# Mechanical_Bridges_AFE.net
KiCad netlist of a schematic drawn in Altium Designer
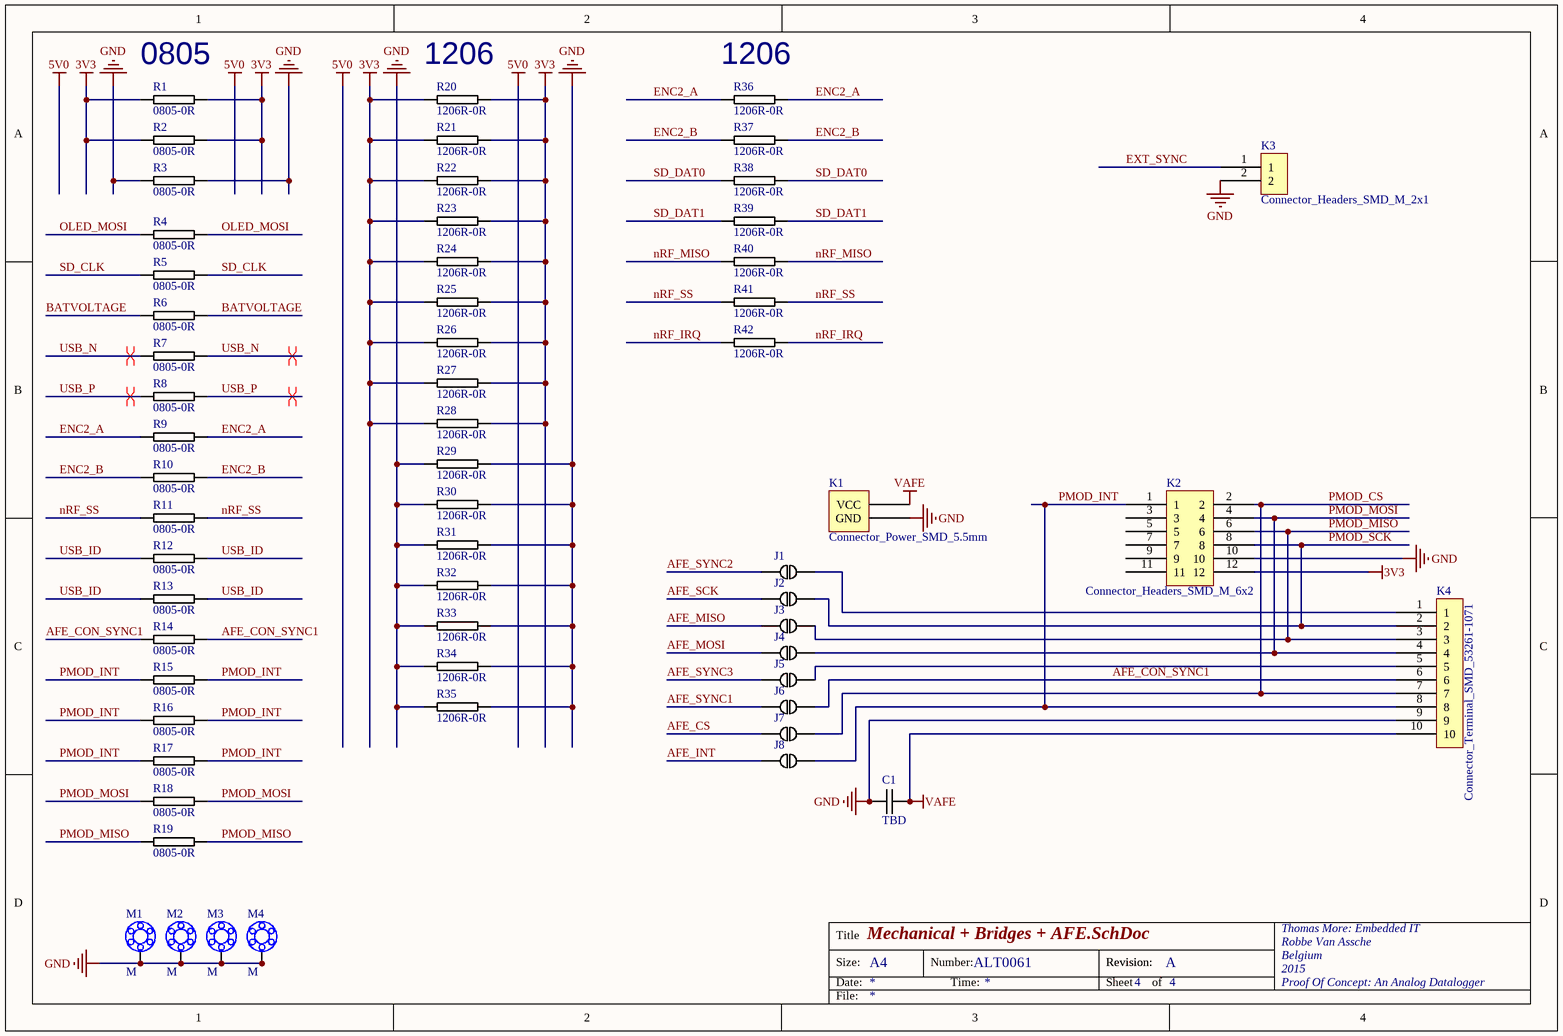
[diagram p0: Mechanical + Bridges + AFE.SchDoc]

(export (version "E")
  (design (tool "Eeschema 10.0.6"))
  (components
    (comp (ref "C1")
      (value "TBD")
      (footprint "1210C-GENERIC")
      (description "CAPACITOR 1210 CERAMIC VALUE TO BE DETERMINED")
      (libsource (lib "RVA_Altium_Library") (part "Passives_Capacitors_1210_1210C-TBD"))
    )
    (comp (ref "J1")
      (value "Connector_Production Connectors_SMD_BYPASS")
      (footprint "BYPASS")
      (description "SOLDERDOT BYPASS")
      (libsource (lib "RVA_Altium_Library") (part "Connector_Production Connectors_SMD_BYPASS"))
    )
    (comp (ref "J2")
      (value "Connector_Production Connectors_SMD_BYPASS")
      (footprint "BYPASS")
      (description "SOLDERDOT BYPASS")
      (libsource (lib "RVA_Altium_Library") (part "Connector_Production Connectors_SMD_BYPASS"))
    )
    (comp (ref "J3")
      (value "Connector_Production Connectors_SMD_BYPASS")
      (footprint "BYPASS")
      (description "SOLDERDOT BYPASS")
      (libsource (lib "RVA_Altium_Library") (part "Connector_Production Connectors_SMD_BYPASS"))
    )
    (comp (ref "J4")
      (value "Connector_Production Connectors_SMD_BYPASS")
      (footprint "BYPASS")
      (description "SOLDERDOT BYPASS")
      (libsource (lib "RVA_Altium_Library") (part "Connector_Production Connectors_SMD_BYPASS"))
    )
    (comp (ref "J5")
      (value "Connector_Production Connectors_SMD_BYPASS")
      (footprint "BYPASS")
      (description "SOLDERDOT BYPASS")
      (libsource (lib "RVA_Altium_Library") (part "Connector_Production Connectors_SMD_BYPASS"))
    )
    (comp (ref "J6")
      (value "Connector_Production Connectors_SMD_BYPASS")
      (footprint "BYPASS")
      (description "SOLDERDOT BYPASS")
      (libsource (lib "RVA_Altium_Library") (part "Connector_Production Connectors_SMD_BYPASS"))
    )
    (comp (ref "J7")
      (value "Connector_Production Connectors_SMD_BYPASS")
      (footprint "BYPASS")
      (description "SOLDERDOT BYPASS")
      (libsource (lib "RVA_Altium_Library") (part "Connector_Production Connectors_SMD_BYPASS"))
    )
    (comp (ref "J8")
      (value "Connector_Production Connectors_SMD_BYPASS")
      (footprint "BYPASS")
      (description "SOLDERDOT BYPASS")
      (libsource (lib "RVA_Altium_Library") (part "Connector_Production Connectors_SMD_BYPASS"))
    )
    (comp (ref "K1")
      (value "Connector_Power_SMD_5.5mm")
      (footprint "ADC-028")
      (description "5.5mm SMD")
      (libsource (lib "RVA_Altium_Library") (part "Connector_Power_SMD_5.5mm"))
    )
    (comp (ref "K2")
      (value "Connector_Headers_SMD_M_6x2")
      (footprint "Header_Male_2.54 6x2")
      (description "SMD Header 6x2")
      (libsource (lib "RVA_Altium_Library") (part "Connector_Headers_SMD_M_6x2"))
    )
    (comp (ref "K3")
      (value "Connector_Headers_SMD_M_2x1")
      (footprint "Header_Male_2.54 2x1")
      (description "SMD Header 2x1")
      (libsource (lib "RVA_Altium_Library") (part "Connector_Headers_SMD_M_2x1"))
    )
    (comp (ref "K4")
      (value "Connector_Terminal_SMD_53261-1071")
      (footprint "53261-1071")
      (description "Picoblade 10p")
      (libsource (lib "RVA_Altium_Library") (part "Connector_Terminal_SMD_53261-1071"))
    )
    (comp (ref "M1")
      (value "M")
      (footprint "MOUNTING")
      (description "MOUNTING HOLE - NON INSTALLABLE")
      (libsource (lib "vh_altium_library") (part "MOUNTING"))
    )
    (comp (ref "M2")
      (value "M")
      (footprint "MOUNTING")
      (description "MOUNTING HOLE - NON INSTALLABLE")
      (libsource (lib "vh_altium_library") (part "MOUNTING"))
    )
    (comp (ref "M3")
      (value "M")
      (footprint "MOUNTING")
      (description "MOUNTING HOLE - NON INSTALLABLE")
      (libsource (lib "vh_altium_library") (part "MOUNTING"))
    )
    (comp (ref "M4")
      (value "M")
      (footprint "MOUNTING")
      (description "MOUNTING HOLE - NON INSTALLABLE")
      (libsource (lib "vh_altium_library") (part "MOUNTING"))
    )
    (comp (ref "R1")
      (value "0805-0R")
      (footprint "0805R-GENERIC")
      (description "RESISTOR 0805 1 WATT")
      (libsource (lib "RVA_Altium_Library") (part "0805R-0R"))
    )
    (comp (ref "R2")
      (value "0805-0R")
      (footprint "0805R-GENERIC")
      (description "RESISTOR 0805 1 WATT")
      (libsource (lib "RVA_Altium_Library") (part "0805R-0R"))
    )
    (comp (ref "R3")
      (value "0805-0R")
      (footprint "0805R-GENERIC")
      (description "RESISTOR 0805 1 WATT")
      (libsource (lib "RVA_Altium_Library") (part "0805R-0R"))
    )
    (comp (ref "R4")
      (value "0805-0R")
      (footprint "0805R-GENERIC")
      (description "RESISTOR 0805 1 WATT")
      (libsource (lib "RVA_Altium_Library") (part "0805R-0R"))
    )
    (comp (ref "R5")
      (value "0805-0R")
      (footprint "0805R-GENERIC")
      (description "RESISTOR 0805 1 WATT")
      (libsource (lib "RVA_Altium_Library") (part "0805R-0R"))
    )
    (comp (ref "R6")
      (value "0805-0R")
      (footprint "0805R-GENERIC")
      (description "RESISTOR 0805 1 WATT")
      (libsource (lib "RVA_Altium_Library") (part "0805R-0R"))
    )
    (comp (ref "R7")
      (value "0805-0R")
      (footprint "0805R-GENERIC")
      (description "RESISTOR 0805 1 WATT")
      (libsource (lib "RVA_Altium_Library") (part "0805R-0R"))
    )
    (comp (ref "R8")
      (value "0805-0R")
      (footprint "0805R-GENERIC")
      (description "RESISTOR 0805 1 WATT")
      (libsource (lib "RVA_Altium_Library") (part "0805R-0R"))
    )
    (comp (ref "R9")
      (value "0805-0R")
      (footprint "0805R-GENERIC")
      (description "RESISTOR 0805 1 WATT")
      (libsource (lib "RVA_Altium_Library") (part "0805R-0R"))
    )
    (comp (ref "R10")
      (value "0805-0R")
      (footprint "0805R-GENERIC")
      (description "RESISTOR 0805 1 WATT")
      (libsource (lib "RVA_Altium_Library") (part "0805R-0R"))
    )
    (comp (ref "R11")
      (value "0805-0R")
      (footprint "0805R-GENERIC")
      (description "RESISTOR 0805 1 WATT")
      (libsource (lib "RVA_Altium_Library") (part "0805R-0R"))
    )
    (comp (ref "R12")
      (value "0805-0R")
      (footprint "0805R-GENERIC")
      (description "RESISTOR 0805 1 WATT")
      (libsource (lib "RVA_Altium_Library") (part "0805R-0R"))
    )
    (comp (ref "R13")
      (value "0805-0R")
      (footprint "0805R-GENERIC")
      (description "RESISTOR 0805 1 WATT")
      (libsource (lib "RVA_Altium_Library") (part "0805R-0R"))
    )
    (comp (ref "R14")
      (value "0805-0R")
      (footprint "0805R-GENERIC")
      (description "RESISTOR 0805 1 WATT")
      (libsource (lib "RVA_Altium_Library") (part "0805R-0R"))
    )
    (comp (ref "R15")
      (value "0805-0R")
      (footprint "0805R-GENERIC")
      (description "RESISTOR 0805 1 WATT")
      (libsource (lib "RVA_Altium_Library") (part "0805R-0R"))
    )
    (comp (ref "R16")
      (value "0805-0R")
      (footprint "0805R-GENERIC")
      (description "RESISTOR 0805 1 WATT")
      (libsource (lib "RVA_Altium_Library") (part "0805R-0R"))
    )
    (comp (ref "R17")
      (value "0805-0R")
      (footprint "0805R-GENERIC")
      (description "RESISTOR 0805 1 WATT")
      (libsource (lib "RVA_Altium_Library") (part "0805R-0R"))
    )
    (comp (ref "R18")
      (value "0805-0R")
      (footprint "0805R-GENERIC")
      (description "RESISTOR 0805 1 WATT")
      (libsource (lib "RVA_Altium_Library") (part "0805R-0R"))
    )
    (comp (ref "R19")
      (value "0805-0R")
      (footprint "0805R-GENERIC")
      (description "RESISTOR 0805 1 WATT")
      (libsource (lib "RVA_Altium_Library") (part "0805R-0R"))
    )
    (comp (ref "R20")
      (value "1206R-0R")
      (footprint "1206R-GENERIC")
      (libsource (lib "RVA_Altium_Library") (part "1206R-0R"))
    )
    (comp (ref "R21")
      (value "1206R-0R")
      (footprint "1206R-GENERIC")
      (libsource (lib "RVA_Altium_Library") (part "1206R-0R"))
    )
    (comp (ref "R22")
      (value "1206R-0R")
      (footprint "1206R-GENERIC")
      (libsource (lib "RVA_Altium_Library") (part "1206R-0R"))
    )
    (comp (ref "R23")
      (value "1206R-0R")
      (footprint "1206R-GENERIC")
      (libsource (lib "RVA_Altium_Library") (part "1206R-0R"))
    )
    (comp (ref "R24")
      (value "1206R-0R")
      (footprint "1206R-GENERIC")
      (libsource (lib "RVA_Altium_Library") (part "1206R-0R"))
    )
    (comp (ref "R25")
      (value "1206R-0R")
      (footprint "1206R-GENERIC")
      (libsource (lib "RVA_Altium_Library") (part "1206R-0R"))
    )
    (comp (ref "R26")
      (value "1206R-0R")
      (footprint "1206R-GENERIC")
      (libsource (lib "RVA_Altium_Library") (part "1206R-0R"))
    )
    (comp (ref "R27")
      (value "1206R-0R")
      (footprint "1206R-GENERIC")
      (libsource (lib "RVA_Altium_Library") (part "1206R-0R"))
    )
    (comp (ref "R28")
      (value "1206R-0R")
      (footprint "1206R-GENERIC")
      (libsource (lib "RVA_Altium_Library") (part "1206R-0R"))
    )
    (comp (ref "R29")
      (value "1206R-0R")
      (footprint "1206R-GENERIC")
      (libsource (lib "RVA_Altium_Library") (part "1206R-0R"))
    )
    (comp (ref "R30")
      (value "1206R-0R")
      (footprint "1206R-GENERIC")
      (libsource (lib "RVA_Altium_Library") (part "1206R-0R"))
    )
    (comp (ref "R31")
      (value "1206R-0R")
      (footprint "1206R-GENERIC")
      (libsource (lib "RVA_Altium_Library") (part "1206R-0R"))
    )
    (comp (ref "R32")
      (value "1206R-0R")
      (footprint "1206R-GENERIC")
      (libsource (lib "RVA_Altium_Library") (part "1206R-0R"))
    )
    (comp (ref "R33")
      (value "1206R-0R")
      (footprint "1206R-GENERIC")
      (libsource (lib "RVA_Altium_Library") (part "1206R-0R"))
    )
    (comp (ref "R34")
      (value "1206R-0R")
      (footprint "1206R-GENERIC")
      (libsource (lib "RVA_Altium_Library") (part "1206R-0R"))
    )
    (comp (ref "R35")
      (value "1206R-0R")
      (footprint "1206R-GENERIC")
      (libsource (lib "RVA_Altium_Library") (part "1206R-0R"))
    )
    (comp (ref "R36")
      (value "1206R-0R")
      (footprint "1206R-GENERIC")
      (libsource (lib "RVA_Altium_Library") (part "1206R-0R"))
    )
    (comp (ref "R37")
      (value "1206R-0R")
      (footprint "1206R-GENERIC")
      (libsource (lib "RVA_Altium_Library") (part "1206R-0R"))
    )
    (comp (ref "R38")
      (value "1206R-0R")
      (footprint "1206R-GENERIC")
      (libsource (lib "RVA_Altium_Library") (part "1206R-0R"))
    )
    (comp (ref "R39")
      (value "1206R-0R")
      (footprint "1206R-GENERIC")
      (libsource (lib "RVA_Altium_Library") (part "1206R-0R"))
    )
    (comp (ref "R40")
      (value "1206R-0R")
      (footprint "1206R-GENERIC")
      (libsource (lib "RVA_Altium_Library") (part "1206R-0R"))
    )
    (comp (ref "R41")
      (value "1206R-0R")
      (footprint "1206R-GENERIC")
      (libsource (lib "RVA_Altium_Library") (part "1206R-0R"))
    )
    (comp (ref "R42")
      (value "1206R-0R")
      (footprint "1206R-GENERIC")
      (libsource (lib "RVA_Altium_Library") (part "1206R-0R"))
    )
  )
  (nets
    (net (code "1") (name "/AFE_CON_SYNC1") (class "Default")
      (node (ref "J6") (pin "2") (pinfunction "2_2") (pintype "passive"))
      (node (ref "K4") (pin "6") (pinfunction "6_6") (pintype "passive"))
      (node (ref "R14") (pin "1") (pintype "passive"))
      (node (ref "R14") (pin "2") (pintype "passive"))
    )
    (net (code "2") (name "/AFE_CS") (class "Default")
      (node (ref "J7") (pin "1") (pinfunction "1_1") (pintype "passive"))
    )
    (net (code "3") (name "/AFE_INT") (class "Default")
      (node (ref "J8") (pin "1") (pinfunction "1_1") (pintype "passive"))
    )
    (net (code "4") (name "/AFE_MISO") (class "Default")
      (node (ref "J3") (pin "1") (pinfunction "1_1") (pintype "passive"))
    )
    (net (code "5") (name "/AFE_MOSI") (class "Default")
      (node (ref "J4") (pin "1") (pinfunction "1_1") (pintype "passive"))
    )
    (net (code "6") (name "/AFE_SCK") (class "Default")
      (node (ref "J2") (pin "1") (pinfunction "1_1") (pintype "passive"))
    )
    (net (code "7") (name "/AFE_SYNC1") (class "Default")
      (node (ref "J6") (pin "1") (pinfunction "1_1") (pintype "passive"))
    )
    (net (code "8") (name "/AFE_SYNC2") (class "Default")
      (node (ref "J1") (pin "1") (pinfunction "1_1") (pintype "passive"))
    )
    (net (code "9") (name "/AFE_SYNC3") (class "Default")
      (node (ref "J5") (pin "1") (pinfunction "1_1") (pintype "passive"))
    )
    (net (code "10") (name "/BATVOLTAGE") (class "Default")
      (node (ref "R6") (pin "1") (pintype "passive"))
      (node (ref "R6") (pin "2") (pintype "passive"))
    )
    (net (code "11") (name "/ENC2_A") (class "Default")
      (node (ref "R36") (pin "1") (pintype "passive"))
      (node (ref "R36") (pin "2") (pintype "passive"))
      (node (ref "R9") (pin "1") (pintype "passive"))
      (node (ref "R9") (pin "2") (pintype "passive"))
    )
    (net (code "12") (name "/ENC2_B") (class "Default")
      (node (ref "R10") (pin "1") (pintype "passive"))
      (node (ref "R10") (pin "2") (pintype "passive"))
      (node (ref "R37") (pin "1") (pintype "passive"))
      (node (ref "R37") (pin "2") (pintype "passive"))
    )
    (net (code "13") (name "/EXT_SYNC") (class "Default")
      (node (ref "K3") (pin "1") (pinfunction "1_1") (pintype "passive"))
    )
    (net (code "14") (name "/OLED_MOSI") (class "Default")
      (node (ref "R4") (pin "1") (pintype "passive"))
      (node (ref "R4") (pin "2") (pintype "passive"))
    )
    (net (code "15") (name "/PMOD_CS") (class "Default")
      (node (ref "J7") (pin "2") (pinfunction "2_2") (pintype "passive"))
      (node (ref "K2") (pin "2") (pinfunction "2_2") (pintype "passive"))
      (node (ref "K4") (pin "7") (pinfunction "7_7") (pintype "passive"))
    )
    (net (code "16") (name "/PMOD_INT") (class "Default")
      (node (ref "J8") (pin "2") (pinfunction "2_2") (pintype "passive"))
      (node (ref "K2") (pin "1") (pinfunction "1_1") (pintype "passive"))
      (node (ref "K4") (pin "8") (pinfunction "8_8") (pintype "passive"))
      (node (ref "R15") (pin "1") (pintype "passive"))
      (node (ref "R15") (pin "2") (pintype "passive"))
      (node (ref "R16") (pin "1") (pintype "passive"))
      (node (ref "R16") (pin "2") (pintype "passive"))
      (node (ref "R17") (pin "1") (pintype "passive"))
      (node (ref "R17") (pin "2") (pintype "passive"))
    )
    (net (code "17") (name "/PMOD_MISO") (class "Default")
      (node (ref "J3") (pin "2") (pinfunction "2_2") (pintype "passive"))
      (node (ref "K2") (pin "6") (pinfunction "6_6") (pintype "passive"))
      (node (ref "K4") (pin "3") (pinfunction "3_3") (pintype "passive"))
      (node (ref "R19") (pin "1") (pintype "passive"))
      (node (ref "R19") (pin "2") (pintype "passive"))
    )
    (net (code "18") (name "/PMOD_MOSI") (class "Default")
      (node (ref "J4") (pin "2") (pinfunction "2_2") (pintype "passive"))
      (node (ref "K2") (pin "4") (pinfunction "4_4") (pintype "passive"))
      (node (ref "K4") (pin "4") (pinfunction "4_4") (pintype "passive"))
      (node (ref "R18") (pin "1") (pintype "passive"))
      (node (ref "R18") (pin "2") (pintype "passive"))
    )
    (net (code "19") (name "/PMOD_SCK") (class "Default")
      (node (ref "J2") (pin "2") (pinfunction "2_2") (pintype "passive"))
      (node (ref "K2") (pin "8") (pinfunction "8_8") (pintype "passive"))
      (node (ref "K4") (pin "2") (pinfunction "2_2") (pintype "passive"))
    )
    (net (code "20") (name "/SD_CLK") (class "Default")
      (node (ref "R5") (pin "1") (pintype "passive"))
      (node (ref "R5") (pin "2") (pintype "passive"))
    )
    (net (code "21") (name "/SD_DAT0") (class "Default")
      (node (ref "R38") (pin "1") (pintype "passive"))
      (node (ref "R38") (pin "2") (pintype "passive"))
    )
    (net (code "22") (name "/SD_DAT1") (class "Default")
      (node (ref "R39") (pin "1") (pintype "passive"))
      (node (ref "R39") (pin "2") (pintype "passive"))
    )
    (net (code "23") (name "/USB_ID") (class "Default")
      (node (ref "R12") (pin "1") (pintype "passive"))
      (node (ref "R12") (pin "2") (pintype "passive"))
      (node (ref "R13") (pin "1") (pintype "passive"))
      (node (ref "R13") (pin "2") (pintype "passive"))
    )
    (net (code "24") (name "/USB_N") (class "Default")
      (node (ref "R7") (pin "1") (pintype "passive"))
      (node (ref "R7") (pin "2") (pintype "passive"))
    )
    (net (code "25") (name "/USB_P") (class "Default")
      (node (ref "R8") (pin "1") (pintype "passive"))
      (node (ref "R8") (pin "2") (pintype "passive"))
    )
    (net (code "26") (name "/nRF_IRQ") (class "Default")
      (node (ref "R42") (pin "1") (pintype "passive"))
      (node (ref "R42") (pin "2") (pintype "passive"))
    )
    (net (code "27") (name "/nRF_MISO") (class "Default")
      (node (ref "R40") (pin "1") (pintype "passive"))
      (node (ref "R40") (pin "2") (pintype "passive"))
    )
    (net (code "28") (name "/nRF_SS") (class "Default")
      (node (ref "R11") (pin "1") (pintype "passive"))
      (node (ref "R11") (pin "2") (pintype "passive"))
      (node (ref "R41") (pin "1") (pintype "passive"))
      (node (ref "R41") (pin "2") (pintype "passive"))
    )
    (net (code "29") (name "3V3") (class "Default")
      (node (ref "K2") (pin "12") (pinfunction "12_12") (pintype "passive"))
      (node (ref "R1") (pin "1") (pintype "passive"))
      (node (ref "R1") (pin "2") (pintype "passive"))
      (node (ref "R2") (pin "1") (pintype "passive"))
      (node (ref "R2") (pin "2") (pintype "passive"))
      (node (ref "R20") (pin "1") (pintype "passive"))
      (node (ref "R20") (pin "2") (pintype "passive"))
      (node (ref "R21") (pin "1") (pintype "passive"))
      (node (ref "R21") (pin "2") (pintype "passive"))
      (node (ref "R22") (pin "1") (pintype "passive"))
      (node (ref "R22") (pin "2") (pintype "passive"))
      (node (ref "R23") (pin "1") (pintype "passive"))
      (node (ref "R23") (pin "2") (pintype "passive"))
      (node (ref "R24") (pin "1") (pintype "passive"))
      (node (ref "R24") (pin "2") (pintype "passive"))
      (node (ref "R25") (pin "1") (pintype "passive"))
      (node (ref "R25") (pin "2") (pintype "passive"))
      (node (ref "R26") (pin "1") (pintype "passive"))
      (node (ref "R26") (pin "2") (pintype "passive"))
      (node (ref "R27") (pin "1") (pintype "passive"))
      (node (ref "R27") (pin "2") (pintype "passive"))
      (node (ref "R28") (pin "1") (pintype "passive"))
      (node (ref "R28") (pin "2") (pintype "passive"))
    )
    (net (code "31") (name "GND") (class "Default")
      (node (ref "C1") (pin "1") (pintype "passive"))
      (node (ref "K1") (pin "GND") (pinfunction "GND_GND") (pintype "power_in"))
      (node (ref "K2") (pin "10") (pinfunction "10_10") (pintype "passive"))
      (node (ref "K3") (pin "2") (pinfunction "2_2") (pintype "passive"))
      (node (ref "K4") (pin "9") (pinfunction "9_9") (pintype "passive"))
      (node (ref "M1") (pin "1") (pinfunction "1_1") (pintype "passive"))
      (node (ref "M1") (pin "2") (pinfunction "2_2") (pintype "passive"))
      (node (ref "M1") (pin "3") (pinfunction "3_3") (pintype "passive"))
      (node (ref "M1") (pin "4") (pinfunction "4_4") (pintype "passive"))
      (node (ref "M1") (pin "5") (pinfunction "5_5") (pintype "passive"))
      (node (ref "M1") (pin "6") (pinfunction "6_6") (pintype "passive"))
      (node (ref "M1") (pin "7") (pinfunction "7_7") (pintype "passive"))
      (node (ref "M2") (pin "1") (pinfunction "1_1") (pintype "passive"))
      (node (ref "M2") (pin "2") (pinfunction "2_2") (pintype "passive"))
      (node (ref "M2") (pin "3") (pinfunction "3_3") (pintype "passive"))
      (node (ref "M2") (pin "4") (pinfunction "4_4") (pintype "passive"))
      (node (ref "M2") (pin "5") (pinfunction "5_5") (pintype "passive"))
      (node (ref "M2") (pin "6") (pinfunction "6_6") (pintype "passive"))
      (node (ref "M2") (pin "7") (pinfunction "7_7") (pintype "passive"))
      (node (ref "M3") (pin "1") (pinfunction "1_1") (pintype "passive"))
      (node (ref "M3") (pin "2") (pinfunction "2_2") (pintype "passive"))
      (node (ref "M3") (pin "3") (pinfunction "3_3") (pintype "passive"))
      (node (ref "M3") (pin "4") (pinfunction "4_4") (pintype "passive"))
      (node (ref "M3") (pin "5") (pinfunction "5_5") (pintype "passive"))
      (node (ref "M3") (pin "6") (pinfunction "6_6") (pintype "passive"))
      (node (ref "M3") (pin "7") (pinfunction "7_7") (pintype "passive"))
      (node (ref "M4") (pin "1") (pinfunction "1_1") (pintype "passive"))
      (node (ref "M4") (pin "2") (pinfunction "2_2") (pintype "passive"))
      (node (ref "M4") (pin "3") (pinfunction "3_3") (pintype "passive"))
      (node (ref "M4") (pin "4") (pinfunction "4_4") (pintype "passive"))
      (node (ref "M4") (pin "5") (pinfunction "5_5") (pintype "passive"))
      (node (ref "M4") (pin "6") (pinfunction "6_6") (pintype "passive"))
      (node (ref "M4") (pin "7") (pinfunction "7_7") (pintype "passive"))
      (node (ref "R29") (pin "1") (pintype "passive"))
      (node (ref "R29") (pin "2") (pintype "passive"))
      (node (ref "R3") (pin "1") (pintype "passive"))
      (node (ref "R3") (pin "2") (pintype "passive"))
      (node (ref "R30") (pin "1") (pintype "passive"))
      (node (ref "R30") (pin "2") (pintype "passive"))
      (node (ref "R31") (pin "1") (pintype "passive"))
      (node (ref "R31") (pin "2") (pintype "passive"))
      (node (ref "R32") (pin "1") (pintype "passive"))
      (node (ref "R32") (pin "2") (pintype "passive"))
      (node (ref "R33") (pin "1") (pintype "passive"))
      (node (ref "R33") (pin "2") (pintype "passive"))
      (node (ref "R34") (pin "1") (pintype "passive"))
      (node (ref "R34") (pin "2") (pintype "passive"))
      (node (ref "R35") (pin "1") (pintype "passive"))
      (node (ref "R35") (pin "2") (pintype "passive"))
    )
    (net (code "32") (name "Net-(J1-Pad2)") (class "Default")
      (node (ref "J1") (pin "2") (pinfunction "2_2") (pintype "passive"))
      (node (ref "K4") (pin "1") (pinfunction "1_1") (pintype "passive"))
    )
    (net (code "33") (name "Net-(J5-Pad2)") (class "Default")
      (node (ref "J5") (pin "2") (pinfunction "2_2") (pintype "passive"))
      (node (ref "K4") (pin "5") (pinfunction "5_5") (pintype "passive"))
    )
    (net (code "34") (name "VAFE") (class "Default")
      (node (ref "C1") (pin "2") (pintype "passive"))
      (node (ref "K1") (pin "VCC") (pinfunction "VCC_VCC") (pintype "power_in"))
      (node (ref "K4") (pin "10") (pinfunction "10_10") (pintype "passive"))
    )
    (net (code "35") (name "unconnected-(K2-Pad3)") (class "Default")
      (node (ref "K2") (pin "3") (pinfunction "3_3") (pintype "passive"))
    )
    (net (code "36") (name "unconnected-(K2-Pad5)") (class "Default")
      (node (ref "K2") (pin "5") (pinfunction "5_5") (pintype "passive"))
    )
    (net (code "37") (name "unconnected-(K2-Pad7)") (class "Default")
      (node (ref "K2") (pin "7") (pinfunction "7_7") (pintype "passive"))
    )
    (net (code "38") (name "unconnected-(K2-Pad9)") (class "Default")
      (node (ref "K2") (pin "9") (pinfunction "9_9") (pintype "passive"))
    )
    (net (code "39") (name "unconnected-(K2-Pad11)") (class "Default")
      (node (ref "K2") (pin "11") (pinfunction "11_11") (pintype "passive"))
    )
  )
)
